# flipdot-matrix.net
KiCad netlist of a schematic drawn in EAGLE
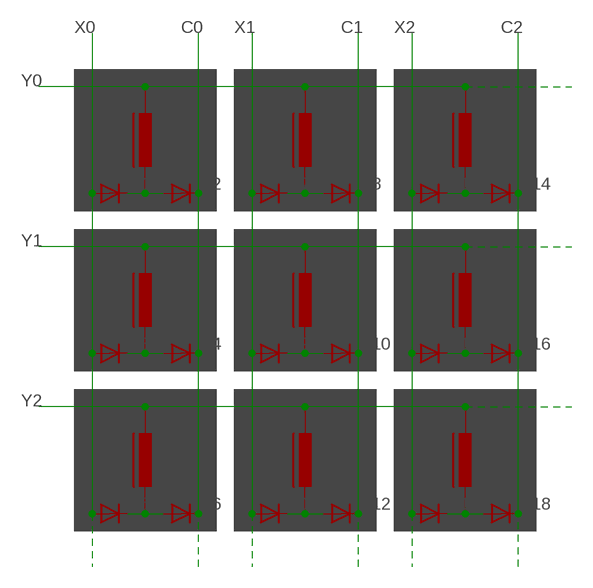
[diagram p0: schematic, sheet 1]
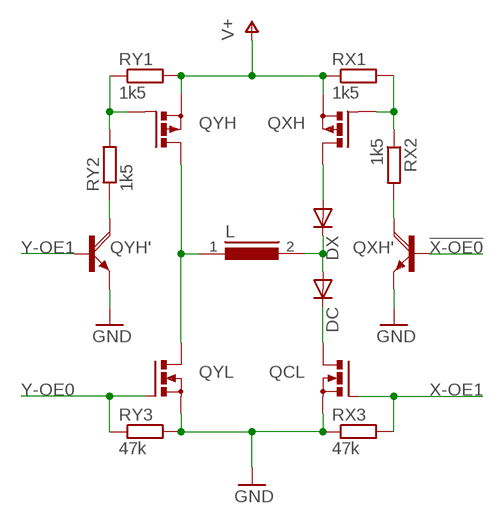
[diagram p1: schematic, sheet 2]

(export (version "E")
  (design (tool "Eeschema 10.0.6"))
  (components
    (comp (ref "DC")
      (value "1N4004")
      (footprint "eagle-import:DO41-10")
      (libsource (lib "eagle-import") (part "1N4004"))
    )
    (comp (ref "DX")
      (value "1N4004")
      (footprint "eagle-import:DO41-10")
      (libsource (lib "eagle-import") (part "1N4004"))
    )
    (comp (ref "L")
      (value "DS10")
      (footprint "eagle-import:DS10")
      (libsource (lib "eagle-import") (part "DS10"))
    )
    (comp (ref "QCL")
      (value "PMOSFET_NTO220BV")
      (footprint "eagle-import:TO220BV")
      (libsource (lib "eagle-import") (part "PMOSFET_NTO220BV"))
    )
    (comp (ref "QXH")
      (value "PMOSFET_PTO220BV")
      (footprint "eagle-import:TO220BV")
      (libsource (lib "eagle-import") (part "PMOSFET_PTO220BV"))
    )
    (comp (ref "QXH'")
      (value "BD679")
      (footprint "eagle-import:TO126AV")
      (libsource (lib "eagle-import") (part "BD679"))
    )
    (comp (ref "QYH")
      (value "PMOSFET_PTO220BV")
      (footprint "eagle-import:TO220BV")
      (libsource (lib "eagle-import") (part "PMOSFET_PTO220BV"))
    )
    (comp (ref "QYH'")
      (value "BD679")
      (footprint "eagle-import:TO126AV")
      (libsource (lib "eagle-import") (part "BD679"))
    )
    (comp (ref "QYL")
      (value "PMOSFET_NTO220BV")
      (footprint "eagle-import:TO220BV")
      (libsource (lib "eagle-import") (part "PMOSFET_NTO220BV"))
    )
    (comp (ref "RX1")
      (value "1k5")
      (footprint "eagle-import:R0603")
      (libsource (lib "eagle-import") (part "R-EU_R0603"))
    )
    (comp (ref "RX2")
      (value "1k5")
      (footprint "eagle-import:R0603")
      (libsource (lib "eagle-import") (part "R-EU_R0603"))
    )
    (comp (ref "RX3")
      (value "47k")
      (footprint "eagle-import:R0603")
      (libsource (lib "eagle-import") (part "R-EU_R0603"))
    )
    (comp (ref "RY1")
      (value "1k5")
      (footprint "eagle-import:R0603")
      (libsource (lib "eagle-import") (part "R-EU_R0603"))
    )
    (comp (ref "RY2")
      (value "1k5")
      (footprint "eagle-import:R0603")
      (libsource (lib "eagle-import") (part "R-EU_R0603"))
    )
    (comp (ref "RY3")
      (value "47k")
      (footprint "eagle-import:R0603")
      (libsource (lib "eagle-import") (part "R-EU_R0603"))
    )
    (comp (ref "D1")
      (value "1N4004")
      (footprint "eagle-import:DO41-10")
      (libsource (lib "eagle-import") (part "1N4004"))
    )
    (comp (ref "D2")
      (value "1N4004")
      (footprint "eagle-import:DO41-10")
      (libsource (lib "eagle-import") (part "1N4004"))
    )
    (comp (ref "D3")
      (value "1N4004")
      (footprint "eagle-import:DO41-10")
      (libsource (lib "eagle-import") (part "1N4004"))
    )
    (comp (ref "D4")
      (value "1N4004")
      (footprint "eagle-import:DO41-10")
      (libsource (lib "eagle-import") (part "1N4004"))
    )
    (comp (ref "D5")
      (value "1N4004")
      (footprint "eagle-import:DO41-10")
      (libsource (lib "eagle-import") (part "1N4004"))
    )
    (comp (ref "D6")
      (value "1N4004")
      (footprint "eagle-import:DO41-10")
      (libsource (lib "eagle-import") (part "1N4004"))
    )
    (comp (ref "D7")
      (value "1N4004")
      (footprint "eagle-import:DO41-10")
      (libsource (lib "eagle-import") (part "1N4004"))
    )
    (comp (ref "D8")
      (value "1N4004")
      (footprint "eagle-import:DO41-10")
      (libsource (lib "eagle-import") (part "1N4004"))
    )
    (comp (ref "D9")
      (value "1N4004")
      (footprint "eagle-import:DO41-10")
      (libsource (lib "eagle-import") (part "1N4004"))
    )
    (comp (ref "D10")
      (value "1N4004")
      (footprint "eagle-import:DO41-10")
      (libsource (lib "eagle-import") (part "1N4004"))
    )
    (comp (ref "D11")
      (value "1N4004")
      (footprint "eagle-import:DO41-10")
      (libsource (lib "eagle-import") (part "1N4004"))
    )
    (comp (ref "D12")
      (value "1N4004")
      (footprint "eagle-import:DO41-10")
      (libsource (lib "eagle-import") (part "1N4004"))
    )
    (comp (ref "D13")
      (value "1N4004")
      (footprint "eagle-import:DO41-10")
      (libsource (lib "eagle-import") (part "1N4004"))
    )
    (comp (ref "D14")
      (value "1N4004")
      (footprint "eagle-import:DO41-10")
      (libsource (lib "eagle-import") (part "1N4004"))
    )
    (comp (ref "D15")
      (value "1N4004")
      (footprint "eagle-import:DO41-10")
      (libsource (lib "eagle-import") (part "1N4004"))
    )
    (comp (ref "D16")
      (value "1N4004")
      (footprint "eagle-import:DO41-10")
      (libsource (lib "eagle-import") (part "1N4004"))
    )
    (comp (ref "D17")
      (value "1N4004")
      (footprint "eagle-import:DO41-10")
      (libsource (lib "eagle-import") (part "1N4004"))
    )
    (comp (ref "D18")
      (value "1N4004")
      (footprint "eagle-import:DO41-10")
      (libsource (lib "eagle-import") (part "1N4004"))
    )
    (comp (ref "L1")
      (value "DS10")
      (footprint "eagle-import:DS10")
      (libsource (lib "eagle-import") (part "DS10"))
    )
    (comp (ref "L2")
      (value "DS10")
      (footprint "eagle-import:DS10")
      (libsource (lib "eagle-import") (part "DS10"))
    )
    (comp (ref "L3")
      (value "DS10")
      (footprint "eagle-import:DS10")
      (libsource (lib "eagle-import") (part "DS10"))
    )
    (comp (ref "L4")
      (value "DS10")
      (footprint "eagle-import:DS10")
      (libsource (lib "eagle-import") (part "DS10"))
    )
    (comp (ref "L5")
      (value "DS10")
      (footprint "eagle-import:DS10")
      (libsource (lib "eagle-import") (part "DS10"))
    )
    (comp (ref "L6")
      (value "DS10")
      (footprint "eagle-import:DS10")
      (libsource (lib "eagle-import") (part "DS10"))
    )
    (comp (ref "L7")
      (value "DS10")
      (footprint "eagle-import:DS10")
      (libsource (lib "eagle-import") (part "DS10"))
    )
    (comp (ref "L8")
      (value "DS10")
      (footprint "eagle-import:DS10")
      (libsource (lib "eagle-import") (part "DS10"))
    )
    (comp (ref "L9")
      (value "DS10")
      (footprint "eagle-import:DS10")
      (libsource (lib "eagle-import") (part "DS10"))
    )
  )
  (nets
    (net (code "1") (name "C0") (class "Default")
      (node (ref "D2") (pin "C") (pinfunction "C_C") (pintype "passive"))
      (node (ref "D4") (pin "C") (pinfunction "C_C") (pintype "passive"))
      (node (ref "D6") (pin "C") (pinfunction "C_C") (pintype "passive"))
    )
    (net (code "2") (name "C1") (class "Default")
      (node (ref "D10") (pin "C") (pinfunction "C_C") (pintype "passive"))
      (node (ref "D12") (pin "C") (pinfunction "C_C") (pintype "passive"))
      (node (ref "D8") (pin "C") (pinfunction "C_C") (pintype "passive"))
    )
    (net (code "3") (name "C2") (class "Default")
      (node (ref "D14") (pin "C") (pinfunction "C_C") (pintype "passive"))
      (node (ref "D16") (pin "C") (pinfunction "C_C") (pintype "passive"))
      (node (ref "D18") (pin "C") (pinfunction "C_C") (pintype "passive"))
    )
    (net (code "4") (name "GND") (class "Default")
      (node (ref "QCL") (pin "S") (pinfunction "S_S") (pintype "passive"))
      (node (ref "QXH'") (pin "E") (pinfunction "E_E") (pintype "passive"))
      (node (ref "QYH'") (pin "E") (pinfunction "E_E") (pintype "passive"))
      (node (ref "QYL") (pin "S") (pinfunction "S_S") (pintype "passive"))
      (node (ref "RX3") (pin "1") (pinfunction "1_1") (pintype "passive"))
      (node (ref "RY3") (pin "2") (pinfunction "2_2") (pintype "passive"))
    )
    (net (code "5") (name "Net-(D1-PadC)") (class "Default")
      (node (ref "D1") (pin "C") (pinfunction "C_C") (pintype "passive"))
      (node (ref "D2") (pin "A") (pinfunction "A_A") (pintype "passive"))
      (node (ref "L1") (pin "1") (pinfunction "1_1") (pintype "passive"))
    )
    (net (code "6") (name "Net-(D3-PadC)") (class "Default")
      (node (ref "D3") (pin "C") (pinfunction "C_C") (pintype "passive"))
      (node (ref "D4") (pin "A") (pinfunction "A_A") (pintype "passive"))
      (node (ref "L2") (pin "1") (pinfunction "1_1") (pintype "passive"))
    )
    (net (code "7") (name "Net-(D5-PadC)") (class "Default")
      (node (ref "D5") (pin "C") (pinfunction "C_C") (pintype "passive"))
      (node (ref "D6") (pin "A") (pinfunction "A_A") (pintype "passive"))
      (node (ref "L3") (pin "1") (pinfunction "1_1") (pintype "passive"))
    )
    (net (code "8") (name "Net-(D7-PadC)") (class "Default")
      (node (ref "D7") (pin "C") (pinfunction "C_C") (pintype "passive"))
      (node (ref "D8") (pin "A") (pinfunction "A_A") (pintype "passive"))
      (node (ref "L4") (pin "1") (pinfunction "1_1") (pintype "passive"))
    )
    (net (code "9") (name "Net-(D10-PadA)") (class "Default")
      (node (ref "D10") (pin "A") (pinfunction "A_A") (pintype "passive"))
      (node (ref "D9") (pin "C") (pinfunction "C_C") (pintype "passive"))
      (node (ref "L5") (pin "1") (pinfunction "1_1") (pintype "passive"))
    )
    (net (code "10") (name "Net-(D11-PadC)") (class "Default")
      (node (ref "D11") (pin "C") (pinfunction "C_C") (pintype "passive"))
      (node (ref "D12") (pin "A") (pinfunction "A_A") (pintype "passive"))
      (node (ref "L6") (pin "1") (pinfunction "1_1") (pintype "passive"))
    )
    (net (code "11") (name "Net-(D13-PadC)") (class "Default")
      (node (ref "D13") (pin "C") (pinfunction "C_C") (pintype "passive"))
      (node (ref "D14") (pin "A") (pinfunction "A_A") (pintype "passive"))
      (node (ref "L7") (pin "1") (pinfunction "1_1") (pintype "passive"))
    )
    (net (code "12") (name "Net-(D15-PadC)") (class "Default")
      (node (ref "D15") (pin "C") (pinfunction "C_C") (pintype "passive"))
      (node (ref "D16") (pin "A") (pinfunction "A_A") (pintype "passive"))
      (node (ref "L8") (pin "1") (pinfunction "1_1") (pintype "passive"))
    )
    (net (code "13") (name "Net-(D17-PadC)") (class "Default")
      (node (ref "D17") (pin "C") (pinfunction "C_C") (pintype "passive"))
      (node (ref "D18") (pin "A") (pinfunction "A_A") (pintype "passive"))
      (node (ref "L9") (pin "1") (pinfunction "1_1") (pintype "passive"))
    )
    (net (code "14") (name "Net-(DC-PadA)") (class "Default")
      (node (ref "DC") (pin "A") (pinfunction "A_A") (pintype "passive"))
      (node (ref "DX") (pin "C") (pinfunction "C_C") (pintype "passive"))
      (node (ref "L") (pin "2") (pinfunction "2_2") (pintype "passive"))
    )
    (net (code "15") (name "Net-(DC-PadC)") (class "Default")
      (node (ref "DC") (pin "C") (pinfunction "C_C") (pintype "passive"))
      (node (ref "QCL") (pin "D") (pinfunction "D_D") (pintype "passive"))
    )
    (net (code "16") (name "Net-(DX-PadA)") (class "Default")
      (node (ref "DX") (pin "A") (pinfunction "A_A") (pintype "passive"))
      (node (ref "QXH") (pin "D") (pinfunction "D_D") (pintype "passive"))
    )
    (net (code "17") (name "Net-(L-Pad1)") (class "Default")
      (node (ref "L") (pin "1") (pinfunction "1_1") (pintype "passive"))
      (node (ref "QYH") (pin "D") (pinfunction "D_D") (pintype "passive"))
      (node (ref "QYL") (pin "D") (pinfunction "D_D") (pintype "passive"))
    )
    (net (code "18") (name "Net-(QXH'-PadC)") (class "Default")
      (node (ref "QXH'") (pin "C") (pinfunction "C_C") (pintype "passive"))
      (node (ref "RX2") (pin "2") (pinfunction "2_2") (pintype "passive"))
    )
    (net (code "19") (name "Net-(QXH-PadG)") (class "Default")
      (node (ref "QXH") (pin "G") (pinfunction "G_G") (pintype "passive"))
      (node (ref "RX1") (pin "2") (pinfunction "2_2") (pintype "passive"))
      (node (ref "RX2") (pin "1") (pinfunction "1_1") (pintype "passive"))
    )
    (net (code "20") (name "Net-(QYH'-PadC)") (class "Default")
      (node (ref "QYH'") (pin "C") (pinfunction "C_C") (pintype "passive"))
      (node (ref "RY2") (pin "1") (pinfunction "1_1") (pintype "passive"))
    )
    (net (code "21") (name "Net-(QYH-PadG)") (class "Default")
      (node (ref "QYH") (pin "G") (pinfunction "G_G") (pintype "passive"))
      (node (ref "RY1") (pin "1") (pinfunction "1_1") (pintype "passive"))
      (node (ref "RY2") (pin "2") (pinfunction "2_2") (pintype "passive"))
    )
    (net (code "22") (name "V+") (class "Default")
      (node (ref "QXH") (pin "S") (pinfunction "S_S") (pintype "passive"))
      (node (ref "QYH") (pin "S") (pinfunction "S_S") (pintype "passive"))
      (node (ref "RX1") (pin "1") (pinfunction "1_1") (pintype "passive"))
      (node (ref "RY1") (pin "2") (pinfunction "2_2") (pintype "passive"))
    )
    (net (code "23") (name "X-OE1") (class "Default")
      (node (ref "QCL") (pin "G") (pinfunction "G_G") (pintype "passive"))
      (node (ref "RX3") (pin "2") (pinfunction "2_2") (pintype "passive"))
    )
    (net (code "24") (name "X0") (class "Default")
      (node (ref "D1") (pin "A") (pinfunction "A_A") (pintype "passive"))
      (node (ref "D3") (pin "A") (pinfunction "A_A") (pintype "passive"))
      (node (ref "D5") (pin "A") (pinfunction "A_A") (pintype "passive"))
    )
    (net (code "25") (name "X1") (class "Default")
      (node (ref "D11") (pin "A") (pinfunction "A_A") (pintype "passive"))
      (node (ref "D7") (pin "A") (pinfunction "A_A") (pintype "passive"))
      (node (ref "D9") (pin "A") (pinfunction "A_A") (pintype "passive"))
    )
    (net (code "26") (name "X2") (class "Default")
      (node (ref "D13") (pin "A") (pinfunction "A_A") (pintype "passive"))
      (node (ref "D15") (pin "A") (pinfunction "A_A") (pintype "passive"))
      (node (ref "D17") (pin "A") (pinfunction "A_A") (pintype "passive"))
    )
    (net (code "27") (name "Y-OE0") (class "Default")
      (node (ref "QYL") (pin "G") (pinfunction "G_G") (pintype "passive"))
      (node (ref "RY3") (pin "1") (pinfunction "1_1") (pintype "passive"))
    )
    (net (code "28") (name "Y-OE1") (class "Default")
      (node (ref "QYH'") (pin "B") (pinfunction "B_B") (pintype "passive"))
    )
    (net (code "29") (name "Y0") (class "Default")
      (node (ref "L1") (pin "2") (pinfunction "2_2") (pintype "passive"))
      (node (ref "L4") (pin "2") (pinfunction "2_2") (pintype "passive"))
      (node (ref "L7") (pin "2") (pinfunction "2_2") (pintype "passive"))
    )
    (net (code "30") (name "Y1") (class "Default")
      (node (ref "L2") (pin "2") (pinfunction "2_2") (pintype "passive"))
      (node (ref "L5") (pin "2") (pinfunction "2_2") (pintype "passive"))
      (node (ref "L8") (pin "2") (pinfunction "2_2") (pintype "passive"))
    )
    (net (code "31") (name "Y2") (class "Default")
      (node (ref "L3") (pin "2") (pinfunction "2_2") (pintype "passive"))
      (node (ref "L6") (pin "2") (pinfunction "2_2") (pintype "passive"))
      (node (ref "L9") (pin "2") (pinfunction "2_2") (pintype "passive"))
    )
    (net (code "32") (name "~{X-OE0}") (class "Default")
      (node (ref "QXH'") (pin "B") (pinfunction "B_B") (pintype "passive"))
    )
  )
)
